# Ex_I2C_Extension.net
KiCad netlist of a schematic drawn in EAGLE
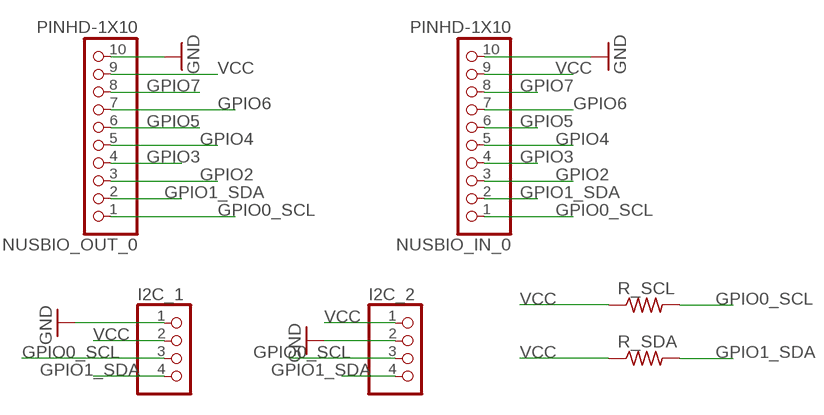
[diagram p0: schematic, sheet 1]

(export (version "E")
  (design (tool "Eeschema 10.0.6"))
  (components
    (comp (ref "I2C_1")
      (value "PINHD-1X4")
      (footprint "eagle-import:1X04")
      (libsource (lib "eagle-import") (part "PINHD-1X4"))
    )
    (comp (ref "I2C_2")
      (value "PINHD-1X4")
      (footprint "eagle-import:1X04")
      (libsource (lib "eagle-import") (part "PINHD-1X4"))
    )
    (comp (ref "NUSBIO_IN_0")
      (value "PINHD-1X10")
      (footprint "eagle-import:1X10-BIG")
      (libsource (lib "eagle-import") (part "PINHD-1X10"))
    )
    (comp (ref "NUSBIO_OUT_0")
      (value "PINHD-1X10")
      (footprint "eagle-import:1X10-BIG")
      (libsource (lib "eagle-import") (part "PINHD-1X10"))
    )
    (comp (ref "R_SCL")
      (value "R-US_R0805")
      (footprint "eagle-import:R0805")
      (libsource (lib "eagle-import") (part "R-US_R0805"))
    )
    (comp (ref "R_SDA")
      (value "R-US_R0805")
      (footprint "eagle-import:R0805")
      (libsource (lib "eagle-import") (part "R-US_R0805"))
    )
  )
  (nets
    (net (code "1") (name "/GPIO0_SCL") (class "Default")
      (node (ref "I2C_1") (pin "3") (pinfunction "3_3") (pintype "passive"))
      (node (ref "I2C_2") (pin "3") (pinfunction "3_3") (pintype "passive"))
      (node (ref "NUSBIO_IN_0") (pin "1") (pinfunction "1_1") (pintype "passive"))
      (node (ref "NUSBIO_OUT_0") (pin "1") (pinfunction "1_1") (pintype "passive"))
      (node (ref "R_SCL") (pin "2") (pinfunction "2_2") (pintype "passive"))
    )
    (net (code "2") (name "/GPIO1_SDA") (class "Default")
      (node (ref "I2C_1") (pin "4") (pinfunction "4_4") (pintype "passive"))
      (node (ref "I2C_2") (pin "4") (pinfunction "4_4") (pintype "passive"))
      (node (ref "NUSBIO_IN_0") (pin "2") (pinfunction "2_2") (pintype "passive"))
      (node (ref "NUSBIO_OUT_0") (pin "2") (pinfunction "2_2") (pintype "passive"))
      (node (ref "R_SDA") (pin "2") (pinfunction "2_2") (pintype "passive"))
    )
    (net (code "3") (name "/GPIO2") (class "Default")
      (node (ref "NUSBIO_IN_0") (pin "3") (pinfunction "3_3") (pintype "passive"))
      (node (ref "NUSBIO_OUT_0") (pin "3") (pinfunction "3_3") (pintype "passive"))
    )
    (net (code "4") (name "/GPIO3") (class "Default")
      (node (ref "NUSBIO_IN_0") (pin "4") (pinfunction "4_4") (pintype "passive"))
      (node (ref "NUSBIO_OUT_0") (pin "4") (pinfunction "4_4") (pintype "passive"))
    )
    (net (code "5") (name "/GPIO4") (class "Default")
      (node (ref "NUSBIO_IN_0") (pin "5") (pinfunction "5_5") (pintype "passive"))
      (node (ref "NUSBIO_OUT_0") (pin "5") (pinfunction "5_5") (pintype "passive"))
    )
    (net (code "6") (name "/GPIO5") (class "Default")
      (node (ref "NUSBIO_IN_0") (pin "6") (pinfunction "6_6") (pintype "passive"))
      (node (ref "NUSBIO_OUT_0") (pin "6") (pinfunction "6_6") (pintype "passive"))
    )
    (net (code "7") (name "/GPIO6") (class "Default")
      (node (ref "NUSBIO_IN_0") (pin "7") (pinfunction "7_7") (pintype "passive"))
      (node (ref "NUSBIO_OUT_0") (pin "7") (pinfunction "7_7") (pintype "passive"))
    )
    (net (code "8") (name "/GPIO7") (class "Default")
      (node (ref "NUSBIO_IN_0") (pin "8") (pinfunction "8_8") (pintype "passive"))
      (node (ref "NUSBIO_OUT_0") (pin "8") (pinfunction "8_8") (pintype "passive"))
    )
    (net (code "9") (name "/VCC") (class "Default")
      (node (ref "I2C_1") (pin "2") (pinfunction "2_2") (pintype "passive"))
      (node (ref "I2C_2") (pin "1") (pinfunction "1_1") (pintype "passive"))
      (node (ref "NUSBIO_IN_0") (pin "9") (pinfunction "9_9") (pintype "passive"))
      (node (ref "NUSBIO_OUT_0") (pin "9") (pinfunction "9_9") (pintype "passive"))
      (node (ref "R_SCL") (pin "1") (pinfunction "1_1") (pintype "passive"))
      (node (ref "R_SDA") (pin "1") (pinfunction "1_1") (pintype "passive"))
    )
    (net (code "10") (name "GND") (class "Default")
      (node (ref "I2C_1") (pin "1") (pinfunction "1_1") (pintype "passive"))
      (node (ref "I2C_2") (pin "2") (pinfunction "2_2") (pintype "passive"))
      (node (ref "NUSBIO_IN_0") (pin "10") (pinfunction "10_10") (pintype "passive"))
      (node (ref "NUSBIO_OUT_0") (pin "10") (pinfunction "10_10") (pintype "passive"))
    )
  )
)
